# Part_J.net
KiCad netlist of a schematic drawn in Altium Designer
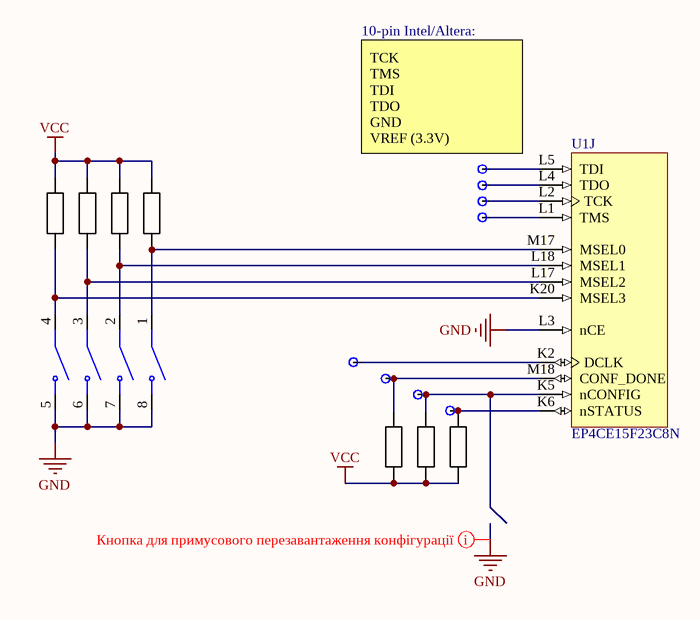
[diagram p0: Part J.SchDoc]

(export (version "E")
  (design (tool "Eeschema 10.0.6"))
  (components
    (comp (ref "J199") (value "Pin1") (footprint "Pin1") (libsource (lib "Schlib1") (part "Pin1")))
    (comp (ref "J200") (value "Pin1") (footprint "Pin1") (libsource (lib "Schlib1") (part "Pin1")))
    (comp (ref "J201") (value "Pin1") (footprint "Pin1") (libsource (lib "Schlib1") (part "Pin1")))
    (comp (ref "J202") (value "Pin1") (footprint "Pin1") (libsource (lib "Schlib1") (part "Pin1")))
    (comp (ref "J203") (value "Pin1") (footprint "Pin1") (libsource (lib "Schlib1") (part "Pin1")))
    (comp (ref "J204") (value "Pin1") (footprint "Pin1") (libsource (lib "Schlib1") (part "Pin1")))
    (comp (ref "J205") (value "Pin1") (footprint "Pin1") (libsource (lib "Schlib1") (part "Pin1")))
    (comp (ref "J206") (value "Pin1") (footprint "Pin1") (libsource (lib "Schlib1") (part "Pin1")))
    (comp (ref "R8")
      (value "10kOm 0603")
      (footprint "RES 0603")
      (libsource (lib "Schlib1") (part "10kOm 0603"))
    )
    (comp (ref "R9")
      (value "10kOm 0603")
      (footprint "RES 0603")
      (libsource (lib "Schlib1") (part "10kOm 0603"))
    )
    (comp (ref "R10")
      (value "10kOm 0603")
      (footprint "RES 0603")
      (libsource (lib "Schlib1") (part "10kOm 0603"))
    )
    (comp (ref "R11")
      (value "10kOm 0603")
      (footprint "RES 0603")
      (libsource (lib "Schlib1") (part "10kOm 0603"))
    )
    (comp (ref "R12")
      (value "10kOm 0603")
      (footprint "RES 0603")
      (libsource (lib "Schlib1") (part "10kOm 0603"))
    )
    (comp (ref "R13")
      (value "10kOm 0603")
      (footprint "RES 0603")
      (libsource (lib "Schlib1") (part "10kOm 0603"))
    )
    (comp (ref "R14")
      (value "10kOm 0603")
      (footprint "RES 0603")
      (libsource (lib "Schlib1") (part "10kOm 0603"))
    )
    (comp (ref "S2")
      (value "206-4")
      (footprint "SW_206-4")
      (fields (field (name "MF") "{'manufacturer': u'CTS Components'}"))
      (libsource (lib "Schlib1") (part "206-4"))
    )
    (comp (ref "U1")
      (value "EP4CE15F23C8N")
      (footprint "FBGA484_A-240")
      (fields (field (name "MANUFACTURER") "Altera"))
      (libsource (lib "Schlib1") (part "FPGA_EP4CE15F23C8N"))
    )
  )
  (nets
    (net (code "1") (name "GND") (class "Default")
      (node (ref "S2") (pin "5") (pinfunction "NO4_5") (pintype "passive"))
      (node (ref "S2") (pin "6") (pinfunction "NO3_6") (pintype "passive"))
      (node (ref "S2") (pin "7") (pinfunction "NO2_7") (pintype "passive"))
      (node (ref "S2") (pin "8") (pinfunction "NO1_8") (pintype "passive"))
      (node (ref "U1") (pin "L3") (pinfunction "nCE_L3") (pintype "input"))
    )
    (net (code "2") (name "Net-(S2-COM1)") (class "Default")
      (node (ref "R11") (pin "1") (pinfunction "1_1") (pintype "passive"))
      (node (ref "S2") (pin "1") (pinfunction "COM1_1") (pintype "passive"))
      (node (ref "U1") (pin "M17") (pinfunction "MSEL0_M17") (pintype "input"))
    )
    (net (code "3") (name "Net-(S2-COM2)") (class "Default")
      (node (ref "R10") (pin "1") (pinfunction "1_1") (pintype "passive"))
      (node (ref "S2") (pin "2") (pinfunction "COM2_2") (pintype "passive"))
      (node (ref "U1") (pin "L18") (pinfunction "MSEL1_L18") (pintype "input"))
    )
    (net (code "4") (name "Net-(S2-COM3)") (class "Default")
      (node (ref "R9") (pin "1") (pinfunction "1_1") (pintype "passive"))
      (node (ref "S2") (pin "3") (pinfunction "COM3_3") (pintype "passive"))
      (node (ref "U1") (pin "L17") (pinfunction "MSEL2_L17") (pintype "input"))
    )
    (net (code "5") (name "Net-(S2-COM4)") (class "Default")
      (node (ref "R8") (pin "1") (pinfunction "1_1") (pintype "passive"))
      (node (ref "S2") (pin "4") (pinfunction "COM4_4") (pintype "passive"))
      (node (ref "U1") (pin "K20") (pinfunction "MSEL3_K20") (pintype "input"))
    )
    (net (code "6") (name "Net-(U1J-CONF_DONE)") (class "Default")
      (node (ref "J204") (pin "1") (pinfunction "1_1") (pintype "passive"))
      (node (ref "R12") (pin "2") (pinfunction "2_2") (pintype "passive"))
      (node (ref "U1") (pin "M18") (pinfunction "CONF_DONE_M18") (pintype "bidirectional"))
    )
    (net (code "7") (name "Net-(U1J-DCLK)") (class "Default")
      (node (ref "J203") (pin "1") (pinfunction "1_1") (pintype "passive"))
      (node (ref "U1") (pin "K2") (pinfunction "DCLK_K2") (pintype "bidirectional"))
    )
    (net (code "8") (name "Net-(U1J-TCK)") (class "Default")
      (node (ref "J201") (pin "1") (pinfunction "1_1") (pintype "passive"))
      (node (ref "U1") (pin "L2") (pinfunction "TCK_L2") (pintype "input"))
    )
    (net (code "9") (name "Net-(U1J-TDI)") (class "Default")
      (node (ref "J199") (pin "1") (pinfunction "1_1") (pintype "passive"))
      (node (ref "U1") (pin "L5") (pinfunction "TDI_L5") (pintype "input"))
    )
    (net (code "10") (name "Net-(U1J-TDO)") (class "Default")
      (node (ref "J200") (pin "1") (pinfunction "1_1") (pintype "passive"))
      (node (ref "U1") (pin "L4") (pinfunction "TDO_L4") (pintype "input"))
    )
    (net (code "11") (name "Net-(U1J-TMS)") (class "Default")
      (node (ref "J202") (pin "1") (pinfunction "1_1") (pintype "passive"))
      (node (ref "U1") (pin "L1") (pinfunction "TMS_L1") (pintype "input"))
    )
    (net (code "12") (name "Net-(U1J-nCONFIG)") (class "Default")
      (node (ref "J205") (pin "1") (pinfunction "1_1") (pintype "passive"))
      (node (ref "R13") (pin "2") (pinfunction "2_2") (pintype "passive"))
      (node (ref "U1") (pin "K5") (pinfunction "nCONFIG_K5") (pintype "input"))
    )
    (net (code "13") (name "Net-(U1J-nSTATUS)") (class "Default")
      (node (ref "J206") (pin "1") (pinfunction "1_1") (pintype "passive"))
      (node (ref "R14") (pin "2") (pinfunction "2_2") (pintype "passive"))
      (node (ref "U1") (pin "K6") (pinfunction "nSTATUS_K6") (pintype "bidirectional"))
    )
    (net (code "14") (name "VCC") (class "Default")
      (node (ref "R10") (pin "2") (pinfunction "2_2") (pintype "passive"))
      (node (ref "R11") (pin "2") (pinfunction "2_2") (pintype "passive"))
      (node (ref "R12") (pin "1") (pinfunction "1_1") (pintype "passive"))
      (node (ref "R13") (pin "1") (pinfunction "1_1") (pintype "passive"))
      (node (ref "R14") (pin "1") (pinfunction "1_1") (pintype "passive"))
      (node (ref "R8") (pin "2") (pinfunction "2_2") (pintype "passive"))
      (node (ref "R9") (pin "2") (pinfunction "2_2") (pintype "passive"))
    )
  )
)
